# IMX6ULL_CORE_sch6.net
KiCad netlist of a schematic drawn in Altium Designer
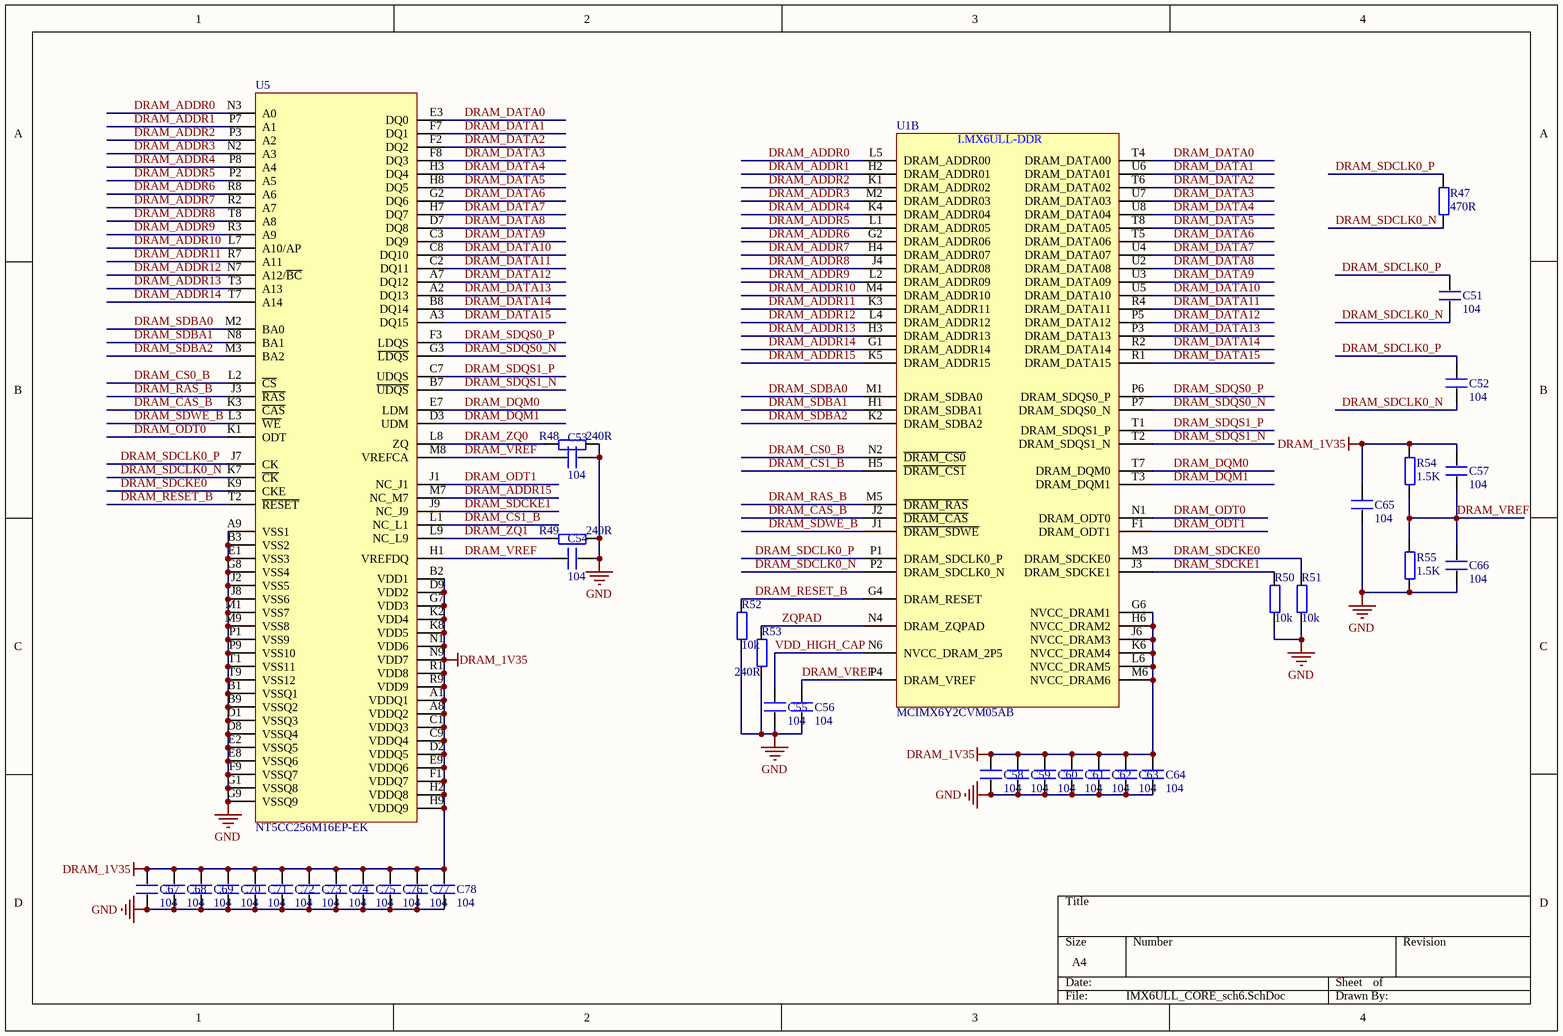
[diagram p0: IMX6ULL_CORE_sch6.SchDoc]

(export (version "E")
  (design (tool "Eeschema 10.0.6"))
  (components
    (comp (ref "C51") (value "104") (footprint "C 0402") (libsource (lib "linux_coreSCHLIB") (part "C")))
    (comp (ref "C52") (value "104") (footprint "C 0402") (libsource (lib "linux_coreSCHLIB") (part "C")))
    (comp (ref "C53") (value "104") (footprint "C 0402") (libsource (lib "linux_coreSCHLIB") (part "C")))
    (comp (ref "C54") (value "104") (footprint "C 0402") (libsource (lib "linux_coreSCHLIB") (part "C")))
    (comp (ref "C55") (value "104") (footprint "C 0402") (libsource (lib "linux_coreSCHLIB") (part "C")))
    (comp (ref "C56") (value "104") (footprint "C 0402") (libsource (lib "linux_coreSCHLIB") (part "C")))
    (comp (ref "C57") (value "104") (footprint "C 0402") (libsource (lib "linux_coreSCHLIB") (part "C")))
    (comp (ref "C58") (value "104") (footprint "C 0402") (libsource (lib "linux_coreSCHLIB") (part "C")))
    (comp (ref "C59") (value "104") (footprint "C 0402") (libsource (lib "linux_coreSCHLIB") (part "C")))
    (comp (ref "C60") (value "104") (footprint "C 0402") (libsource (lib "linux_coreSCHLIB") (part "C")))
    (comp (ref "C61") (value "104") (footprint "C 0402") (libsource (lib "linux_coreSCHLIB") (part "C")))
    (comp (ref "C62") (value "104") (footprint "C 0402") (libsource (lib "linux_coreSCHLIB") (part "C")))
    (comp (ref "C63") (value "104") (footprint "C 0402") (libsource (lib "linux_coreSCHLIB") (part "C")))
    (comp (ref "C64") (value "104") (footprint "C 0402") (libsource (lib "linux_coreSCHLIB") (part "C")))
    (comp (ref "C65") (value "104") (footprint "C 0402") (libsource (lib "linux_coreSCHLIB") (part "C")))
    (comp (ref "C66") (value "104") (footprint "C 0402") (libsource (lib "linux_coreSCHLIB") (part "C")))
    (comp (ref "C67") (value "104") (footprint "C 0402") (libsource (lib "linux_coreSCHLIB") (part "C")))
    (comp (ref "C68") (value "104") (footprint "C 0402") (libsource (lib "linux_coreSCHLIB") (part "C")))
    (comp (ref "C69") (value "104") (footprint "C 0402") (libsource (lib "linux_coreSCHLIB") (part "C")))
    (comp (ref "C70") (value "104") (footprint "C 0402") (libsource (lib "linux_coreSCHLIB") (part "C")))
    (comp (ref "C71") (value "104") (footprint "C 0402") (libsource (lib "linux_coreSCHLIB") (part "C")))
    (comp (ref "C72") (value "104") (footprint "C 0402") (libsource (lib "linux_coreSCHLIB") (part "C")))
    (comp (ref "C73") (value "104") (footprint "C 0402") (libsource (lib "linux_coreSCHLIB") (part "C")))
    (comp (ref "C74") (value "104") (footprint "C 0402") (libsource (lib "linux_coreSCHLIB") (part "C")))
    (comp (ref "C75") (value "104") (footprint "C 0402") (libsource (lib "linux_coreSCHLIB") (part "C")))
    (comp (ref "C76") (value "104") (footprint "C 0402") (libsource (lib "linux_coreSCHLIB") (part "C")))
    (comp (ref "C77") (value "104") (footprint "C 0402") (libsource (lib "linux_coreSCHLIB") (part "C")))
    (comp (ref "C78") (value "104") (footprint "C 0402") (libsource (lib "linux_coreSCHLIB") (part "C")))
    (comp (ref "R47") (value "470R") (footprint "R 0402") (libsource (lib "linux_coreSCHLIB") (part "R")))
    (comp (ref "R48") (value "240R") (footprint "R 0402") (libsource (lib "linux_coreSCHLIB") (part "R")))
    (comp (ref "R49") (value "240R") (footprint "R 0402") (libsource (lib "linux_coreSCHLIB") (part "R")))
    (comp (ref "R50") (value "10k") (footprint "R 0402") (libsource (lib "linux_coreSCHLIB") (part "R")))
    (comp (ref "R51") (value "10k") (footprint "R 0402") (libsource (lib "linux_coreSCHLIB") (part "R")))
    (comp (ref "R52") (value "10k") (footprint "R 0402") (libsource (lib "linux_coreSCHLIB") (part "R")))
    (comp (ref "R53") (value "240R") (footprint "R 0402") (libsource (lib "linux_coreSCHLIB") (part "R")))
    (comp (ref "R54") (value "1.5K") (footprint "R 0402") (libsource (lib "linux_coreSCHLIB") (part "R")))
    (comp (ref "R55") (value "1.5K") (footprint "R 0402") (libsource (lib "linux_coreSCHLIB") (part "R")))
    (comp (ref "U1")
      (value "MCIMX6Y2CVM05AB")
      (footprint "BGA289C80P17X17_1400X1400X132")
      (libsource (lib "linux_coreSCHLIB") (part "MCIMX6Y2CVM05AB"))
    )
    (comp (ref "U5")
      (value "NT5CC256M16EP-EK")
      (footprint "BGA96")
      (libsource (lib "linux_coreSCHLIB") (part "MT41K256M16TW"))
    )
  )
  (nets
    (net (code "1") (name "/DRAM_ADDR0") (class "Default")
      (node (ref "U1") (pin "L5") (pinfunction "DRAM_ADDR00_L5") (pintype "passive"))
      (node (ref "U5") (pin "N3") (pinfunction "A0_N3") (pintype "passive"))
    )
    (net (code "2") (name "/DRAM_ADDR1") (class "Default")
      (node (ref "U1") (pin "H2") (pinfunction "DRAM_ADDR01_H2") (pintype "passive"))
      (node (ref "U5") (pin "P7") (pinfunction "A1_P7") (pintype "passive"))
    )
    (net (code "3") (name "/DRAM_ADDR2") (class "Default")
      (node (ref "U1") (pin "K1") (pinfunction "DRAM_ADDR02_K1") (pintype "passive"))
      (node (ref "U5") (pin "P3") (pinfunction "A2_P3") (pintype "passive"))
    )
    (net (code "4") (name "/DRAM_ADDR3") (class "Default")
      (node (ref "U1") (pin "M2") (pinfunction "DRAM_ADDR03_M2") (pintype "passive"))
      (node (ref "U5") (pin "N2") (pinfunction "A3_N2") (pintype "passive"))
    )
    (net (code "5") (name "/DRAM_ADDR4") (class "Default")
      (node (ref "U1") (pin "K4") (pinfunction "DRAM_ADDR04_K4") (pintype "passive"))
      (node (ref "U5") (pin "P8") (pinfunction "A4_P8") (pintype "passive"))
    )
    (net (code "6") (name "/DRAM_ADDR5") (class "Default")
      (node (ref "U1") (pin "L1") (pinfunction "DRAM_ADDR05_L1") (pintype "passive"))
      (node (ref "U5") (pin "P2") (pinfunction "A5_P2") (pintype "passive"))
    )
    (net (code "7") (name "/DRAM_ADDR6") (class "Default")
      (node (ref "U1") (pin "G2") (pinfunction "DRAM_ADDR06_G2") (pintype "passive"))
      (node (ref "U5") (pin "R8") (pinfunction "A6_R8") (pintype "passive"))
    )
    (net (code "8") (name "/DRAM_ADDR7") (class "Default")
      (node (ref "U1") (pin "H4") (pinfunction "DRAM_ADDR07_H4") (pintype "passive"))
      (node (ref "U5") (pin "R2") (pinfunction "A7_R2") (pintype "passive"))
    )
    (net (code "9") (name "/DRAM_ADDR8") (class "Default")
      (node (ref "U1") (pin "J4") (pinfunction "DRAM_ADDR08_J4") (pintype "passive"))
      (node (ref "U5") (pin "T8") (pinfunction "A8_T8") (pintype "passive"))
    )
    (net (code "10") (name "/DRAM_ADDR9") (class "Default")
      (node (ref "U1") (pin "L2") (pinfunction "DRAM_ADDR09_L2") (pintype "passive"))
      (node (ref "U5") (pin "R3") (pinfunction "A9_R3") (pintype "passive"))
    )
    (net (code "11") (name "/DRAM_ADDR10") (class "Default")
      (node (ref "U1") (pin "M4") (pinfunction "DRAM_ADDR10_M4") (pintype "passive"))
      (node (ref "U5") (pin "L7") (pinfunction "A10/AP_L7") (pintype "passive"))
    )
    (net (code "12") (name "/DRAM_ADDR11") (class "Default")
      (node (ref "U1") (pin "K3") (pinfunction "DRAM_ADDR11_K3") (pintype "passive"))
      (node (ref "U5") (pin "R7") (pinfunction "A11_R7") (pintype "passive"))
    )
    (net (code "13") (name "/DRAM_ADDR12") (class "Default")
      (node (ref "U1") (pin "L4") (pinfunction "DRAM_ADDR12_L4") (pintype "passive"))
      (node (ref "U5") (pin "N7") (pinfunction "A12/~{BC}_N7") (pintype "passive"))
    )
    (net (code "14") (name "/DRAM_ADDR13") (class "Default")
      (node (ref "U1") (pin "H3") (pinfunction "DRAM_ADDR13_H3") (pintype "passive"))
      (node (ref "U5") (pin "T3") (pinfunction "A13_T3") (pintype "passive"))
    )
    (net (code "15") (name "/DRAM_ADDR14") (class "Default")
      (node (ref "U1") (pin "G1") (pinfunction "DRAM_ADDR14_G1") (pintype "passive"))
      (node (ref "U5") (pin "T7") (pinfunction "A14_T7") (pintype "passive"))
    )
    (net (code "16") (name "/DRAM_ADDR15") (class "Default")
      (node (ref "U1") (pin "K5") (pinfunction "DRAM_ADDR15_K5") (pintype "passive"))
      (node (ref "U5") (pin "M7") (pinfunction "NC_M7_M7") (pintype "passive"))
    )
    (net (code "17") (name "/DRAM_CAS_B") (class "Default")
      (node (ref "U1") (pin "J2") (pinfunction "~{DRAM_CAS}_J2") (pintype "passive"))
      (node (ref "U5") (pin "K3") (pinfunction "~{CAS}_K3") (pintype "passive"))
    )
    (net (code "18") (name "/DRAM_CS0_B") (class "Default")
      (node (ref "U1") (pin "N2") (pinfunction "~{DRAM_CS0}_N2") (pintype "passive"))
      (node (ref "U5") (pin "L2") (pinfunction "~{CS}_L2") (pintype "passive"))
    )
    (net (code "19") (name "/DRAM_CS1_B") (class "Default")
      (node (ref "U1") (pin "H5") (pinfunction "~{DRAM_CS1}_H5") (pintype "passive"))
      (node (ref "U5") (pin "L1") (pinfunction "NC_L1_L1") (pintype "passive"))
    )
    (net (code "20") (name "/DRAM_DATA0") (class "Default")
      (node (ref "U1") (pin "T4") (pinfunction "DRAM_DATA00_T4") (pintype "passive"))
      (node (ref "U5") (pin "E3") (pinfunction "DQ0_E3") (pintype "passive"))
    )
    (net (code "21") (name "/DRAM_DATA1") (class "Default")
      (node (ref "U1") (pin "U6") (pinfunction "DRAM_DATA01_U6") (pintype "passive"))
      (node (ref "U5") (pin "F7") (pinfunction "DQ1_F7") (pintype "passive"))
    )
    (net (code "22") (name "/DRAM_DATA2") (class "Default")
      (node (ref "U1") (pin "T6") (pinfunction "DRAM_DATA02_T6") (pintype "passive"))
      (node (ref "U5") (pin "F2") (pinfunction "DQ2_F2") (pintype "passive"))
    )
    (net (code "23") (name "/DRAM_DATA3") (class "Default")
      (node (ref "U1") (pin "U7") (pinfunction "DRAM_DATA03_U7") (pintype "passive"))
      (node (ref "U5") (pin "F8") (pinfunction "DQ3_F8") (pintype "passive"))
    )
    (net (code "24") (name "/DRAM_DATA4") (class "Default")
      (node (ref "U1") (pin "U8") (pinfunction "DRAM_DATA04_U8") (pintype "passive"))
      (node (ref "U5") (pin "H3") (pinfunction "DQ4_H3") (pintype "passive"))
    )
    (net (code "25") (name "/DRAM_DATA5") (class "Default")
      (node (ref "U1") (pin "T8") (pinfunction "DRAM_DATA05_T8") (pintype "passive"))
      (node (ref "U5") (pin "H8") (pinfunction "DQ5_H8") (pintype "passive"))
    )
    (net (code "26") (name "/DRAM_DATA6") (class "Default")
      (node (ref "U1") (pin "T5") (pinfunction "DRAM_DATA06_T5") (pintype "passive"))
      (node (ref "U5") (pin "G2") (pinfunction "DQ6_G2") (pintype "passive"))
    )
    (net (code "27") (name "/DRAM_DATA7") (class "Default")
      (node (ref "U1") (pin "U4") (pinfunction "DRAM_DATA07_U4") (pintype "passive"))
      (node (ref "U5") (pin "H7") (pinfunction "DQ7_H7") (pintype "passive"))
    )
    (net (code "28") (name "/DRAM_DATA8") (class "Default")
      (node (ref "U1") (pin "U2") (pinfunction "DRAM_DATA08_U2") (pintype "passive"))
      (node (ref "U5") (pin "D7") (pinfunction "DQ8_D7") (pintype "passive"))
    )
    (net (code "29") (name "/DRAM_DATA9") (class "Default")
      (node (ref "U1") (pin "U3") (pinfunction "DRAM_DATA09_U3") (pintype "passive"))
      (node (ref "U5") (pin "C3") (pinfunction "DQ9_C3") (pintype "passive"))
    )
    (net (code "30") (name "/DRAM_DATA10") (class "Default")
      (node (ref "U1") (pin "U5") (pinfunction "DRAM_DATA10_U5") (pintype "passive"))
      (node (ref "U5") (pin "C8") (pinfunction "DQ10_C8") (pintype "passive"))
    )
    (net (code "31") (name "/DRAM_DATA11") (class "Default")
      (node (ref "U1") (pin "R4") (pinfunction "DRAM_DATA11_R4") (pintype "passive"))
      (node (ref "U5") (pin "C2") (pinfunction "DQ11_C2") (pintype "passive"))
    )
    (net (code "32") (name "/DRAM_DATA12") (class "Default")
      (node (ref "U1") (pin "P5") (pinfunction "DRAM_DATA12_P5") (pintype "passive"))
      (node (ref "U5") (pin "A7") (pinfunction "DQ12_A7") (pintype "passive"))
    )
    (net (code "33") (name "/DRAM_DATA13") (class "Default")
      (node (ref "U1") (pin "P3") (pinfunction "DRAM_DATA13_P3") (pintype "passive"))
      (node (ref "U5") (pin "A2") (pinfunction "DQ13_A2") (pintype "passive"))
    )
    (net (code "34") (name "/DRAM_DATA14") (class "Default")
      (node (ref "U1") (pin "R2") (pinfunction "DRAM_DATA14_R2") (pintype "passive"))
      (node (ref "U5") (pin "B8") (pinfunction "DQ14_B8") (pintype "passive"))
    )
    (net (code "35") (name "/DRAM_DATA15") (class "Default")
      (node (ref "U1") (pin "R1") (pinfunction "DRAM_DATA15_R1") (pintype "passive"))
      (node (ref "U5") (pin "A3") (pinfunction "DQ15_A3") (pintype "passive"))
    )
    (net (code "36") (name "/DRAM_DQM0") (class "Default")
      (node (ref "U1") (pin "T7") (pinfunction "DRAM_DQM0_T7") (pintype "passive"))
      (node (ref "U5") (pin "E7") (pinfunction "LDM_E7") (pintype "passive"))
    )
    (net (code "37") (name "/DRAM_DQM1") (class "Default")
      (node (ref "U1") (pin "T3") (pinfunction "DRAM_DQM1_T3") (pintype "passive"))
      (node (ref "U5") (pin "D3") (pinfunction "UDM_D3") (pintype "passive"))
    )
    (net (code "38") (name "/DRAM_ODT0") (class "Default")
      (node (ref "U1") (pin "N1") (pinfunction "DRAM_ODT0_N1") (pintype "passive"))
      (node (ref "U5") (pin "K1") (pinfunction "ODT_K1") (pintype "passive"))
    )
    (net (code "39") (name "/DRAM_ODT1") (class "Default")
      (node (ref "U1") (pin "F1") (pinfunction "DRAM_ODT1_F1") (pintype "passive"))
      (node (ref "U5") (pin "J1") (pinfunction "NC_J1_J1") (pintype "passive"))
    )
    (net (code "40") (name "/DRAM_RAS_B") (class "Default")
      (node (ref "U1") (pin "M5") (pinfunction "~{DRAM_RAS}_M5") (pintype "passive"))
      (node (ref "U5") (pin "J3") (pinfunction "~{RAS}_J3") (pintype "passive"))
    )
    (net (code "41") (name "/DRAM_RESET_B") (class "Default")
      (node (ref "R52") (pin "2") (pintype "passive"))
      (node (ref "U1") (pin "G4") (pinfunction "DRAM_RESET_G4") (pintype "passive"))
      (node (ref "U5") (pin "T2") (pinfunction "~{RESET}_T2") (pintype "passive"))
    )
    (net (code "42") (name "/DRAM_SDBA0") (class "Default")
      (node (ref "U1") (pin "M1") (pinfunction "DRAM_SDBA0_M1") (pintype "passive"))
      (node (ref "U5") (pin "M2") (pinfunction "BA0_M2") (pintype "passive"))
    )
    (net (code "43") (name "/DRAM_SDBA1") (class "Default")
      (node (ref "U1") (pin "H1") (pinfunction "DRAM_SDBA1_H1") (pintype "passive"))
      (node (ref "U5") (pin "N8") (pinfunction "BA1_N8") (pintype "passive"))
    )
    (net (code "44") (name "/DRAM_SDBA2") (class "Default")
      (node (ref "U1") (pin "K2") (pinfunction "DRAM_SDBA2_K2") (pintype "passive"))
      (node (ref "U5") (pin "M3") (pinfunction "BA2_M3") (pintype "passive"))
    )
    (net (code "45") (name "/DRAM_SDCKE0") (class "Default")
      (node (ref "R51") (pin "2") (pintype "passive"))
      (node (ref "U1") (pin "M3") (pinfunction "DRAM_SDCKE0_M3") (pintype "passive"))
      (node (ref "U5") (pin "K9") (pinfunction "CKE_K9") (pintype "passive"))
    )
    (net (code "46") (name "/DRAM_SDCKE1") (class "Default")
      (node (ref "R50") (pin "2") (pintype "passive"))
      (node (ref "U1") (pin "J3") (pinfunction "DRAM_SDCKE1_J3") (pintype "passive"))
      (node (ref "U5") (pin "J9") (pinfunction "NC_J9_J9") (pintype "passive"))
    )
    (net (code "47") (name "/DRAM_SDCLK0_N") (class "Default")
      (node (ref "C51") (pin "1") (pintype "passive"))
      (node (ref "C52") (pin "1") (pintype "passive"))
      (node (ref "R47") (pin "1") (pintype "passive"))
      (node (ref "U1") (pin "P2") (pinfunction "DRAM_SDCLK0_N_P2") (pintype "passive"))
      (node (ref "U5") (pin "K7") (pinfunction "~{CK}_K7") (pintype "passive"))
    )
    (net (code "48") (name "/DRAM_SDCLK0_P") (class "Default")
      (node (ref "C51") (pin "2") (pintype "passive"))
      (node (ref "C52") (pin "2") (pintype "passive"))
      (node (ref "R47") (pin "2") (pintype "passive"))
      (node (ref "U1") (pin "P1") (pinfunction "DRAM_SDCLK0_P_P1") (pintype "passive"))
      (node (ref "U5") (pin "J7") (pinfunction "CK_J7") (pintype "passive"))
    )
    (net (code "49") (name "/DRAM_SDQS0_N") (class "Default")
      (node (ref "U1") (pin "P7") (pinfunction "DRAM_SDQS0_N_P7") (pintype "passive"))
      (node (ref "U5") (pin "G3") (pinfunction "~{LDQS}_G3") (pintype "passive"))
    )
    (net (code "50") (name "/DRAM_SDQS0_P") (class "Default")
      (node (ref "U1") (pin "P6") (pinfunction "DRAM_SDQS0_P_P6") (pintype "passive"))
      (node (ref "U5") (pin "F3") (pinfunction "LDQS_F3") (pintype "passive"))
    )
    (net (code "51") (name "/DRAM_SDQS1_N") (class "Default")
      (node (ref "U1") (pin "T2") (pinfunction "DRAM_SDQS1_N_T2") (pintype "passive"))
      (node (ref "U5") (pin "B7") (pinfunction "~{UDQS}_B7") (pintype "passive"))
    )
    (net (code "52") (name "/DRAM_SDQS1_P") (class "Default")
      (node (ref "U1") (pin "T1") (pinfunction "DRAM_SDQS1_P_T1") (pintype "passive"))
      (node (ref "U5") (pin "C7") (pinfunction "UDQS_C7") (pintype "passive"))
    )
    (net (code "53") (name "/DRAM_SDWE_B") (class "Default")
      (node (ref "U1") (pin "J1") (pinfunction "~{DRAM_SDWE}_J1") (pintype "passive"))
      (node (ref "U5") (pin "L3") (pinfunction "~{WE}_L3") (pintype "passive"))
    )
    (net (code "54") (name "/DRAM_VREF") (class "Default")
      (node (ref "C53") (pin "1") (pintype "passive"))
      (node (ref "C54") (pin "1") (pintype "passive"))
      (node (ref "C56") (pin "2") (pintype "passive"))
      (node (ref "C57") (pin "1") (pintype "passive"))
      (node (ref "C66") (pin "2") (pintype "passive"))
      (node (ref "R54") (pin "1") (pintype "passive"))
      (node (ref "R55") (pin "2") (pintype "passive"))
      (node (ref "U1") (pin "P4") (pinfunction "DRAM_VREF_P4") (pintype "passive"))
      (node (ref "U5") (pin "H1") (pinfunction "VREFDQ_H1") (pintype "passive"))
      (node (ref "U5") (pin "M8") (pinfunction "VREFCA_M8") (pintype "passive"))
    )
    (net (code "55") (name "/DRAM_ZQ0") (class "Default")
      (node (ref "R48") (pin "1") (pintype "passive"))
      (node (ref "U5") (pin "L8") (pinfunction "ZQ_L8") (pintype "passive"))
    )
    (net (code "56") (name "/DRAM_ZQ1") (class "Default")
      (node (ref "R49") (pin "1") (pintype "passive"))
      (node (ref "U5") (pin "L9") (pinfunction "NC_L9_L9") (pintype "passive"))
    )
    (net (code "57") (name "/VDD_HIGH_CAP") (class "Default")
      (node (ref "C55") (pin "2") (pintype "passive"))
      (node (ref "U1") (pin "N6") (pinfunction "NVCC_DRAM_2P5_N6") (pintype "passive"))
    )
    (net (code "58") (name "/ZQPAD") (class "Default")
      (node (ref "R53") (pin "2") (pintype "passive"))
      (node (ref "U1") (pin "N4") (pinfunction "DRAM_ZQPAD_N4") (pintype "passive"))
    )
    (net (code "59") (name "DRAM_1V35") (class "Default")
      (node (ref "C57") (pin "2") (pintype "passive"))
      (node (ref "C58") (pin "2") (pintype "passive"))
      (node (ref "C59") (pin "2") (pintype "passive"))
      (node (ref "C60") (pin "2") (pintype "passive"))
      (node (ref "C61") (pin "2") (pintype "passive"))
      (node (ref "C62") (pin "2") (pintype "passive"))
      (node (ref "C63") (pin "2") (pintype "passive"))
      (node (ref "C64") (pin "2") (pintype "passive"))
      (node (ref "C65") (pin "2") (pintype "passive"))
      (node (ref "C67") (pin "2") (pintype "passive"))
      (node (ref "C68") (pin "2") (pintype "passive"))
      (node (ref "C69") (pin "2") (pintype "passive"))
      (node (ref "C70") (pin "2") (pintype "passive"))
      (node (ref "C71") (pin "2") (pintype "passive"))
      (node (ref "C72") (pin "2") (pintype "passive"))
      (node (ref "C73") (pin "2") (pintype "passive"))
      (node (ref "C74") (pin "2") (pintype "passive"))
      (node (ref "C75") (pin "2") (pintype "passive"))
      (node (ref "C76") (pin "2") (pintype "passive"))
      (node (ref "C77") (pin "2") (pintype "passive"))
      (node (ref "C78") (pin "2") (pintype "passive"))
      (node (ref "R54") (pin "2") (pintype "passive"))
      (node (ref "U1") (pin "G6") (pinfunction "NVCC_DRAM1_G6") (pintype "passive"))
      (node (ref "U1") (pin "H6") (pinfunction "NVCC_DRAM2_H6") (pintype "passive"))
      (node (ref "U1") (pin "J6") (pinfunction "NVCC_DRAM3_J6") (pintype "passive"))
      (node (ref "U1") (pin "K6") (pinfunction "NVCC_DRAM4_K6") (pintype "passive"))
      (node (ref "U1") (pin "L6") (pinfunction "NVCC_DRAM5_L6") (pintype "passive"))
      (node (ref "U1") (pin "M6") (pinfunction "NVCC_DRAM6_M6") (pintype "passive"))
      (node (ref "U5") (pin "A1") (pinfunction "VDDQ1_A1") (pintype "passive"))
      (node (ref "U5") (pin "A8") (pinfunction "VDDQ2_A8") (pintype "passive"))
      (node (ref "U5") (pin "B2") (pinfunction "VDD1_B2") (pintype "passive"))
      (node (ref "U5") (pin "C1") (pinfunction "VDDQ3_C1") (pintype "passive"))
      (node (ref "U5") (pin "C9") (pinfunction "VDDQ4_C9") (pintype "passive"))
      (node (ref "U5") (pin "D2") (pinfunction "VDDQ5_D2") (pintype "passive"))
      (node (ref "U5") (pin "D9") (pinfunction "VDD2_D9") (pintype "passive"))
      (node (ref "U5") (pin "E9") (pinfunction "VDDQ6_E9") (pintype "passive"))
      (node (ref "U5") (pin "F1") (pinfunction "VDDQ7_F1") (pintype "passive"))
      (node (ref "U5") (pin "G7") (pinfunction "VDD3_G7") (pintype "passive"))
      (node (ref "U5") (pin "H2") (pinfunction "VDDQ8_H2") (pintype "passive"))
      (node (ref "U5") (pin "H9") (pinfunction "VDDQ9_H9") (pintype "passive"))
      (node (ref "U5") (pin "K2") (pinfunction "VDD4_K2") (pintype "passive"))
      (node (ref "U5") (pin "K8") (pinfunction "VDD5_K8") (pintype "passive"))
      (node (ref "U5") (pin "N1") (pinfunction "VDD6_N1") (pintype "passive"))
      (node (ref "U5") (pin "N9") (pinfunction "VDD7_N9") (pintype "passive"))
      (node (ref "U5") (pin "R1") (pinfunction "VDD8_R1") (pintype "passive"))
      (node (ref "U5") (pin "R9") (pinfunction "VDD9_R9") (pintype "passive"))
    )
    (net (code "60") (name "GND") (class "Default")
      (node (ref "C53") (pin "2") (pintype "passive"))
      (node (ref "C54") (pin "2") (pintype "passive"))
      (node (ref "C55") (pin "1") (pintype "passive"))
      (node (ref "C56") (pin "1") (pintype "passive"))
      (node (ref "C58") (pin "1") (pintype "passive"))
      (node (ref "C59") (pin "1") (pintype "passive"))
      (node (ref "C60") (pin "1") (pintype "passive"))
      (node (ref "C61") (pin "1") (pintype "passive"))
      (node (ref "C62") (pin "1") (pintype "passive"))
      (node (ref "C63") (pin "1") (pintype "passive"))
      (node (ref "C64") (pin "1") (pintype "passive"))
      (node (ref "C65") (pin "1") (pintype "passive"))
      (node (ref "C66") (pin "1") (pintype "passive"))
      (node (ref "C67") (pin "1") (pintype "passive"))
      (node (ref "C68") (pin "1") (pintype "passive"))
      (node (ref "C69") (pin "1") (pintype "passive"))
      (node (ref "C70") (pin "1") (pintype "passive"))
      (node (ref "C71") (pin "1") (pintype "passive"))
      (node (ref "C72") (pin "1") (pintype "passive"))
      (node (ref "C73") (pin "1") (pintype "passive"))
      (node (ref "C74") (pin "1") (pintype "passive"))
      (node (ref "C75") (pin "1") (pintype "passive"))
      (node (ref "C76") (pin "1") (pintype "passive"))
      (node (ref "C77") (pin "1") (pintype "passive"))
      (node (ref "C78") (pin "1") (pintype "passive"))
      (node (ref "R48") (pin "2") (pintype "passive"))
      (node (ref "R49") (pin "2") (pintype "passive"))
      (node (ref "R50") (pin "1") (pintype "passive"))
      (node (ref "R51") (pin "1") (pintype "passive"))
      (node (ref "R52") (pin "1") (pintype "passive"))
      (node (ref "R53") (pin "1") (pintype "passive"))
      (node (ref "R55") (pin "1") (pintype "passive"))
      (node (ref "U5") (pin "A9") (pinfunction "VSS1_A9") (pintype "passive"))
      (node (ref "U5") (pin "B1") (pinfunction "VSSQ1_B1") (pintype "passive"))
      (node (ref "U5") (pin "B3") (pinfunction "VSS2_B3") (pintype "passive"))
      (node (ref "U5") (pin "B9") (pinfunction "VSSQ2_B9") (pintype "passive"))
      (node (ref "U5") (pin "D1") (pinfunction "VSSQ3_D1") (pintype "passive"))
      (node (ref "U5") (pin "D8") (pinfunction "VSSQ4_D8") (pintype "passive"))
      (node (ref "U5") (pin "E1") (pinfunction "VSS3_E1") (pintype "passive"))
      (node (ref "U5") (pin "E2") (pinfunction "VSSQ5_E2") (pintype "passive"))
      (node (ref "U5") (pin "E8") (pinfunction "VSSQ6_E8") (pintype "passive"))
      (node (ref "U5") (pin "F9") (pinfunction "VSSQ7_F9") (pintype "passive"))
      (node (ref "U5") (pin "G1") (pinfunction "VSSQ8_G1") (pintype "passive"))
      (node (ref "U5") (pin "G8") (pinfunction "VSS4_G8") (pintype "passive"))
      (node (ref "U5") (pin "G9") (pinfunction "VSSQ9_G9") (pintype "passive"))
      (node (ref "U5") (pin "J2") (pinfunction "VSS5_J2") (pintype "passive"))
      (node (ref "U5") (pin "J8") (pinfunction "VSS6_J8") (pintype "passive"))
      (node (ref "U5") (pin "M1") (pinfunction "VSS7_M1") (pintype "passive"))
      (node (ref "U5") (pin "M9") (pinfunction "VSS8_M9") (pintype "passive"))
      (node (ref "U5") (pin "P1") (pinfunction "VSS9_P1") (pintype "passive"))
      (node (ref "U5") (pin "P9") (pinfunction "VSS10_P9") (pintype "passive"))
      (node (ref "U5") (pin "T1") (pinfunction "VSS11_T1") (pintype "passive"))
      (node (ref "U5") (pin "T9") (pinfunction "VSS12_T9") (pintype "passive"))
    )
  )
)
